# 02_IO_Interface.net
KiCad netlist of a schematic drawn in Altium Designer
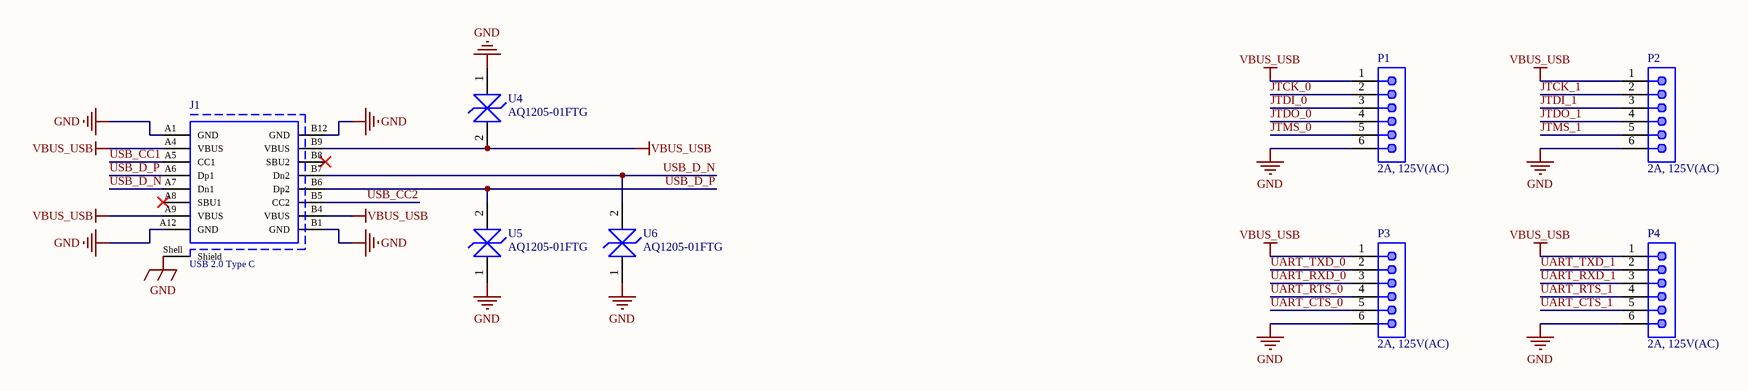
[diagram p0: 02_IO_Interface.SchDoc]

(export (version "E")
  (design (tool "Eeschema 10.0.6"))
  (components
    (comp (ref "J1")
      (value "USB 2.0 Type C")
      (footprint "USB4105-GF-A")
      (description "USB Connectors USB Type C,2.0, Rec,SMT, 0.95mmTH Shell Stakes,G/F,RA,Top Mnt,T&R")
      (fields (field (name "LCSC PART #") "C2765186") (field (name "MANUFACTURER") "GCT"))
      (libsource (lib "Altium_USB") (part "USB4105-GF-A"))
    )
    (comp (ref "P1")
      (value "2A, 125V(AC)")
      (footprint "62000611622")
      (description "WR-WTB Male Vertical Shrouded Header, pitch 2mm, 6p")
      (fields (field (name "PART NUMBER") "62000611622") (field (name "MANUFACTURER") "Wurth Elektronik"))
      (libsource (lib "Altium_PCB_Connector") (part "62000611622"))
    )
    (comp (ref "P2")
      (value "2A, 125V(AC)")
      (footprint "62000611622")
      (description "WR-WTB Male Vertical Shrouded Header, pitch 2mm, 6p")
      (fields (field (name "PART NUMBER") "62000611622") (field (name "MANUFACTURER") "Wurth Elektronik"))
      (libsource (lib "Altium_PCB_Connector") (part "62000611622"))
    )
    (comp (ref "P3")
      (value "2A, 125V(AC)")
      (footprint "62000611622")
      (description "WR-WTB Male Vertical Shrouded Header, pitch 2mm, 6p")
      (fields (field (name "PART NUMBER") "62000611622") (field (name "MANUFACTURER") "Wurth Elektronik"))
      (libsource (lib "Altium_PCB_Connector") (part "62000611622"))
    )
    (comp (ref "P4")
      (value "2A, 125V(AC)")
      (footprint "62000611622")
      (description "WR-WTB Male Vertical Shrouded Header, pitch 2mm, 6p")
      (fields (field (name "PART NUMBER") "62000611622") (field (name "MANUFACTURER") "Wurth Elektronik"))
      (libsource (lib "Altium_PCB_Connector") (part "62000611622"))
    )
    (comp (ref "U4")
      (value "AQ1205-01FTG")
      (footprint "SOD323")
      (description "ESD Suppressors / TVS Diodes 5V 7A 30kV SOD323 Bi-dir TVS")
      (fields (field (name "MANUFACTURER") "Littelfuse"))
      (libsource (lib "Altium_ESD") (part "AQ1205-01FTG"))
    )
    (comp (ref "U5")
      (value "AQ1205-01FTG")
      (footprint "SOD323")
      (description "ESD Suppressors / TVS Diodes 5V 7A 30kV SOD323 Bi-dir TVS")
      (fields (field (name "MANUFACTURER") "Littelfuse"))
      (libsource (lib "Altium_ESD") (part "AQ1205-01FTG"))
    )
    (comp (ref "U6")
      (value "AQ1205-01FTG")
      (footprint "SOD323")
      (description "ESD Suppressors / TVS Diodes 5V 7A 30kV SOD323 Bi-dir TVS")
      (fields (field (name "MANUFACTURER") "Littelfuse"))
      (libsource (lib "Altium_ESD") (part "AQ1205-01FTG"))
    )
  )
  (nets
    (net (code "1") (name "/JTCK_0") (class "Default")
      (node (ref "P1") (pin "2") (pinfunction "2_2") (pintype "passive"))
    )
    (net (code "2") (name "/JTCK_1") (class "Default")
      (node (ref "P2") (pin "2") (pinfunction "2_2") (pintype "passive"))
    )
    (net (code "3") (name "/JTDI_0") (class "Default")
      (node (ref "P1") (pin "3") (pinfunction "3_3") (pintype "passive"))
    )
    (net (code "4") (name "/JTDI_1") (class "Default")
      (node (ref "P2") (pin "3") (pinfunction "3_3") (pintype "passive"))
    )
    (net (code "5") (name "/JTDO_0") (class "Default")
      (node (ref "P1") (pin "4") (pinfunction "4_4") (pintype "passive"))
    )
    (net (code "6") (name "/JTDO_1") (class "Default")
      (node (ref "P2") (pin "4") (pinfunction "4_4") (pintype "passive"))
    )
    (net (code "7") (name "/JTMS_0") (class "Default")
      (node (ref "P1") (pin "5") (pinfunction "5_5") (pintype "passive"))
    )
    (net (code "8") (name "/JTMS_1") (class "Default")
      (node (ref "P2") (pin "5") (pinfunction "5_5") (pintype "passive"))
    )
    (net (code "9") (name "/UART_CTS_0") (class "Default")
      (node (ref "P3") (pin "5") (pinfunction "5_5") (pintype "passive"))
    )
    (net (code "10") (name "/UART_CTS_1") (class "Default")
      (node (ref "P4") (pin "5") (pinfunction "5_5") (pintype "passive"))
    )
    (net (code "11") (name "/UART_RTS_0") (class "Default")
      (node (ref "P3") (pin "4") (pinfunction "4_4") (pintype "passive"))
    )
    (net (code "12") (name "/UART_RTS_1") (class "Default")
      (node (ref "P4") (pin "4") (pinfunction "4_4") (pintype "passive"))
    )
    (net (code "13") (name "/UART_RXD_0") (class "Default")
      (node (ref "P3") (pin "3") (pinfunction "3_3") (pintype "passive"))
    )
    (net (code "14") (name "/UART_RXD_1") (class "Default")
      (node (ref "P4") (pin "3") (pinfunction "3_3") (pintype "passive"))
    )
    (net (code "15") (name "/UART_TXD_0") (class "Default")
      (node (ref "P3") (pin "2") (pinfunction "2_2") (pintype "passive"))
    )
    (net (code "16") (name "/UART_TXD_1") (class "Default")
      (node (ref "P4") (pin "2") (pinfunction "2_2") (pintype "passive"))
    )
    (net (code "17") (name "/USB_CC1") (class "Default")
      (node (ref "J1") (pin "A5") (pinfunction "CC1_A5") (pintype "passive"))
    )
    (net (code "18") (name "/USB_CC2") (class "Default")
      (node (ref "J1") (pin "B5") (pinfunction "CC2_B5") (pintype "passive"))
    )
    (net (code "19") (name "/USB_D_N") (class "Default")
      (node (ref "J1") (pin "A7") (pinfunction "Dn1_A7") (pintype "passive"))
      (node (ref "J1") (pin "B7") (pinfunction "Dn2_B7") (pintype "passive"))
      (node (ref "U6") (pin "2") (pinfunction "2_2") (pintype "passive"))
    )
    (net (code "20") (name "/USB_D_P") (class "Default")
      (node (ref "J1") (pin "A6") (pinfunction "Dp1_A6") (pintype "passive"))
      (node (ref "J1") (pin "B6") (pinfunction "Dp2_B6") (pintype "passive"))
      (node (ref "U5") (pin "2") (pinfunction "2_2") (pintype "passive"))
    )
    (net (code "21") (name "GND") (class "Default")
      (node (ref "J1") (pin "A1") (pinfunction "GND_A1") (pintype "passive"))
      (node (ref "J1") (pin "A12") (pinfunction "GND_A12") (pintype "passive"))
      (node (ref "J1") (pin "B1") (pinfunction "GND_B1") (pintype "passive"))
      (node (ref "J1") (pin "B12") (pinfunction "GND_B12") (pintype "passive"))
      (node (ref "J1") (pin "Shell") (pinfunction "Shield_Shell") (pintype "passive"))
      (node (ref "P1") (pin "6") (pinfunction "6_6") (pintype "passive"))
      (node (ref "P2") (pin "6") (pinfunction "6_6") (pintype "passive"))
      (node (ref "P3") (pin "6") (pinfunction "6_6") (pintype "passive"))
      (node (ref "P4") (pin "6") (pinfunction "6_6") (pintype "passive"))
      (node (ref "U4") (pin "1") (pinfunction "1_1") (pintype "passive"))
      (node (ref "U5") (pin "1") (pinfunction "1_1") (pintype "passive"))
      (node (ref "U6") (pin "1") (pinfunction "1_1") (pintype "passive"))
    )
    (net (code "22") (name "VBUS_USB") (class "Default")
      (node (ref "J1") (pin "A4") (pinfunction "VBUS_A4") (pintype "passive"))
      (node (ref "J1") (pin "A9") (pinfunction "VBUS_A9") (pintype "passive"))
      (node (ref "J1") (pin "B4") (pinfunction "VBUS_B4") (pintype "passive"))
      (node (ref "J1") (pin "B9") (pinfunction "VBUS_B9") (pintype "passive"))
      (node (ref "P1") (pin "1") (pinfunction "1_1") (pintype "passive"))
      (node (ref "P2") (pin "1") (pinfunction "1_1") (pintype "passive"))
      (node (ref "P3") (pin "1") (pinfunction "1_1") (pintype "passive"))
      (node (ref "P4") (pin "1") (pinfunction "1_1") (pintype "passive"))
      (node (ref "U4") (pin "2") (pinfunction "2_2") (pintype "passive"))
    )
    (net (code "23") (name "unconnected-(J1-SBU1-PadA8)") (class "Default")
      (node (ref "J1") (pin "A8") (pinfunction "SBU1_A8") (pintype "passive+no_connect"))
    )
    (net (code "24") (name "unconnected-(J1-SBU2-PadB8)") (class "Default")
      (node (ref "J1") (pin "B8") (pinfunction "SBU2_B8") (pintype "passive+no_connect"))
    )
  )
)
